# Main.net
KiCad netlist of a schematic drawn in Altium Designer
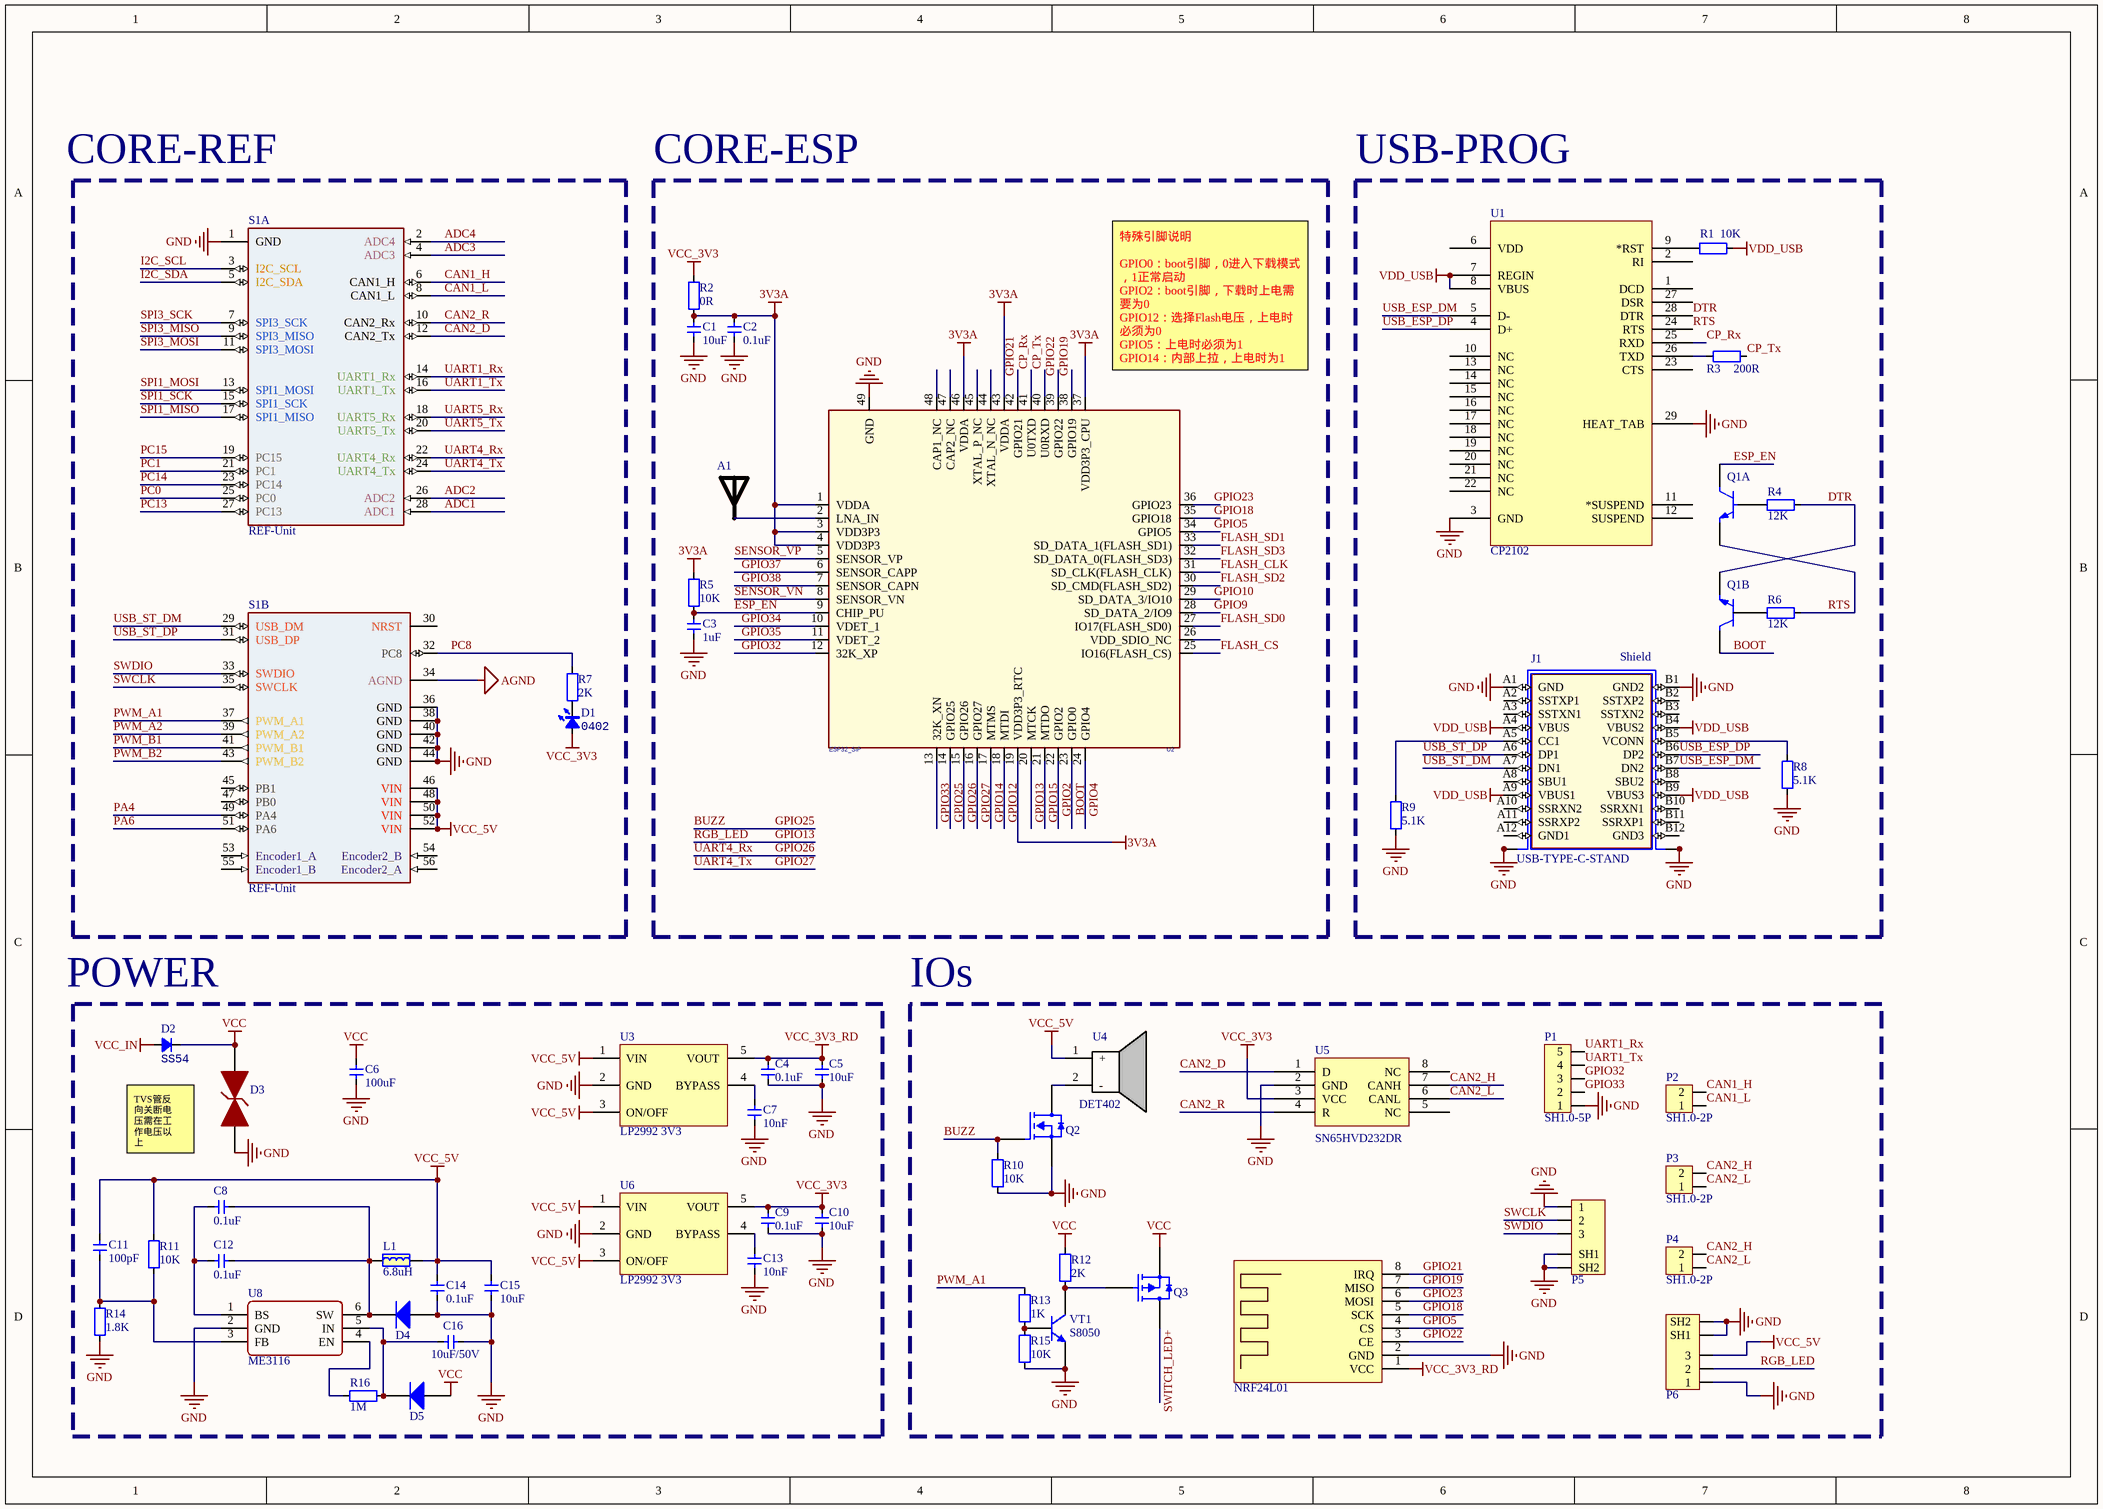
[diagram p0: Main.SchDoc]

(export (version "E")
  (design (tool "Eeschema 10.0.6"))
  (components
    (comp (ref "A1")
      (value "RAINSUN")
      (footprint "ANT-Rainsun-AN5120")
      (libsource (lib "MyPcbLib") (part "ANT-Rainsun-AP5120"))
    )
    (comp (ref "C1")
      (value "10uF")
      (footprint "CAP_0402")
      (description "Capacitor")
      (libsource (lib "MyPcbLib") (part "电容-0402"))
    )
    (comp (ref "C2")
      (value "0.1uF")
      (footprint "CAP_0402")
      (description "Capacitor")
      (libsource (lib "MyPcbLib") (part "电容-0402"))
    )
    (comp (ref "C3")
      (value "1uF")
      (footprint "CAP_0402")
      (description "Capacitor")
      (libsource (lib "MyPcbLib") (part "电容-0402"))
    )
    (comp (ref "C4")
      (value "0.1uF")
      (footprint "CAP_0402")
      (description "Capacitor")
      (libsource (lib "MyPcbLib") (part "电容-0402"))
    )
    (comp (ref "C5")
      (value "10uF")
      (footprint "CAP_0402")
      (description "Capacitor")
      (libsource (lib "MyPcbLib") (part "电容-0402"))
    )
    (comp (ref "C6")
      (value "100uF")
      (footprint "1206-CAP")
      (description "Capacitor")
      (libsource (lib "MyPcbLib") (part "电容-1206"))
    )
    (comp (ref "C7")
      (value "10nF")
      (footprint "CAP_0402")
      (description "Capacitor")
      (libsource (lib "MyPcbLib") (part "电容-0402"))
    )
    (comp (ref "C8")
      (value "0.1uF")
      (footprint "CAP_0402")
      (description "Capacitor")
      (libsource (lib "MyPcbLib") (part "电容-0402"))
    )
    (comp (ref "C9")
      (value "0.1uF")
      (footprint "CAP_0402")
      (description "Capacitor")
      (libsource (lib "MyPcbLib") (part "电容-0402"))
    )
    (comp (ref "C10")
      (value "10uF")
      (footprint "CAP_0402")
      (description "Capacitor")
      (libsource (lib "MyPcbLib") (part "电容-0402"))
    )
    (comp (ref "C11")
      (value "100pF")
      (footprint "CAP_0402")
      (description "Capacitor")
      (libsource (lib "MyPcbLib") (part "电容-0402"))
    )
    (comp (ref "C12")
      (value "0.1uF")
      (footprint "CAP_0402")
      (description "Capacitor")
      (libsource (lib "MyPcbLib") (part "电容-0402"))
    )
    (comp (ref "C13")
      (value "10nF")
      (footprint "CAP_0402")
      (description "Capacitor")
      (libsource (lib "MyPcbLib") (part "电容-0402"))
    )
    (comp (ref "C14")
      (value "0.1uF")
      (footprint "CAP_0402")
      (description "Capacitor")
      (libsource (lib "MyPcbLib") (part "电容-0402"))
    )
    (comp (ref "C15")
      (value "10uF")
      (footprint "CAP_0402")
      (description "Capacitor")
      (libsource (lib "MyPcbLib") (part "电容-0402"))
    )
    (comp (ref "C16")
      (value "10uF/50V")
      (footprint "CAP_0402")
      (description "Capacitor")
      (libsource (lib "MyPcbLib") (part "电容-0402"))
    )
    (comp (ref "D1")
      (value "color?")
      (footprint "LED_0402_RED")
      (description "LED")
      (fields (field (name "TYPE") "0402"))
      (libsource (lib "KitSprout") (part "LED_0402"))
    )
    (comp (ref "D2")
      (value "SS54")
      (footprint "DO-214AC")
      (description "Diode")
      (libsource (lib "KitSprout") (part "Diode_SMA"))
    )
    (comp (ref "D3")
      (value "SMBJ28CA")
      (footprint "SMBJ-CA_MFG")
      (libsource (lib "MyPcbLib") (part "SMBJ28CA"))
    )
    (comp (ref "D4")
      (value "二极管-5819W")
      (footprint "SOD-323")
      (description "40V")
      (libsource (lib "MyPcbLib") (part "二极管-5819W"))
    )
    (comp (ref "D5")
      (value "二极管-5819W")
      (footprint "SOD-323")
      (description "40V")
      (libsource (lib "MyPcbLib") (part "二极管-5819W"))
    )
    (comp (ref "J1")
      (value "USB-TYPE-C-STAND")
      (footprint "USB-TYPE-C-STAND")
      (fields (field (name "MP") "632722110112") (field (name "MF") "Wurth Electronics"))
      (libsource (lib "MyPcbLib") (part "USB-TYPE-C-STAND"))
    )
    (comp (ref "L1") (value "6.8uH") (footprint "IND-201612") (libsource (lib "MyPcbLib") (part "电感-201612")))
    (comp (ref "P1") (value "SH1.0-5P") (footprint "SH1.0-5P") (libsource (lib "MyPcbLib") (part "SH1.0-5P")))
    (comp (ref "P2") (value "SH1.0-2P") (footprint "SH1.0-2P") (libsource (lib "MyPcbLib") (part "SH1.0-2P")))
    (comp (ref "P3") (value "SH1.0-2P") (footprint "SH1.0-2P") (libsource (lib "MyPcbLib") (part "SH1.0-2P")))
    (comp (ref "P4") (value "SH1.0-2P") (footprint "SH1.0-2P") (libsource (lib "MyPcbLib") (part "SH1.0-2P")))
    (comp (ref "P5")
      (value "SH1.0-3P")
      (footprint "SH1.0-3P")
      (description "Header")
      (libsource (lib "") (part "SH1.0-3P_1"))
    )
    (comp (ref "P6")
      (value "SH1.0-3P")
      (footprint "SH1.0-3P")
      (description "Header")
      (libsource (lib "MyPcbLib") (part "SH1.0-3P"))
    )
    (comp (ref "Q1")
      (value "BC847BVC-7")
      (footprint "SOT563-6")
      (libsource (lib "MyPcbLib") (part "BC847BVC-7"))
    )
    (comp (ref "Q2")
      (value "AO3400A")
      (footprint "SOT23-3")
      (description "N-MOS")
      (libsource (lib "MyPcbLib") (part "AO3400A"))
    )
    (comp (ref "Q3")
      (value "AO3401A")
      (footprint "SOT23-3")
      (description "P-MOS")
      (libsource (lib "MyPcbLib") (part "AO3401A"))
    )
    (comp (ref "R1")
      (value "10K")
      (footprint "RES_0402")
      (description "Resistor")
      (libsource (lib "") (part "电阻-0402_1"))
    )
    (comp (ref "R2")
      (value "0R")
      (footprint "RES_0402")
      (description "Resistor")
      (libsource (lib "MyPcbLib") (part "电阻-0402"))
    )
    (comp (ref "R3")
      (value "200R")
      (footprint "RES_0402")
      (description "Resistor")
      (libsource (lib "") (part "电阻-0402_1"))
    )
    (comp (ref "R4")
      (value "12K")
      (footprint "RES_0402")
      (description "Resistor")
      (libsource (lib "") (part "电阻-0402_1"))
    )
    (comp (ref "R5")
      (value "10K")
      (footprint "RES_0402")
      (description "Resistor")
      (libsource (lib "MyPcbLib") (part "电阻-0402"))
    )
    (comp (ref "R6")
      (value "12K")
      (footprint "RES_0402")
      (description "Resistor")
      (libsource (lib "") (part "电阻-0402_1"))
    )
    (comp (ref "R7")
      (value "2K")
      (footprint "RES_0402")
      (description "Resistor")
      (libsource (lib "MyPcbLib") (part "电阻-0402"))
    )
    (comp (ref "R8")
      (value "5.1K")
      (footprint "RES_0402")
      (description "Resistor")
      (libsource (lib "MyPcbLib") (part "电阻-0402"))
    )
    (comp (ref "R9")
      (value "5.1K")
      (footprint "RES_0402")
      (description "Resistor")
      (libsource (lib "MyPcbLib") (part "电阻-0402"))
    )
    (comp (ref "R10")
      (value "10K")
      (footprint "RES_0402")
      (description "Resistor")
      (libsource (lib "") (part "电阻-0402_2"))
    )
    (comp (ref "R11")
      (value "10K")
      (footprint "RES_0402")
      (description "Resistor")
      (libsource (lib "") (part "电阻-0402_2"))
    )
    (comp (ref "R12")
      (value "2K")
      (footprint "RES_0402")
      (description "Resistor")
      (libsource (lib "") (part "电阻-0402_2"))
    )
    (comp (ref "R13")
      (value "1K")
      (footprint "RES_0402")
      (description "Resistor")
      (libsource (lib "MyPcbLib") (part "电阻-0402"))
    )
    (comp (ref "R14")
      (value "1.8K")
      (footprint "RES_0402")
      (description "Resistor")
      (libsource (lib "") (part "电阻-0402_2"))
    )
    (comp (ref "R15")
      (value "10K")
      (footprint "RES_0402")
      (description "Resistor")
      (libsource (lib "MyPcbLib") (part "电阻-0402"))
    )
    (comp (ref "R16")
      (value "1M")
      (footprint "RES_0402")
      (description "Resistor")
      (libsource (lib "") (part "电阻-0402_1"))
    )
    (comp (ref "S1")
      (value "REF-Unit")
      (footprint "REF-UNIT")
      (description "Robot Embedded Framework based on STM43F405RGT6.")
      (libsource (lib "SOM") (part "REF-Unit"))
    )
    (comp (ref "U1")
      (value "CP2102")
      (footprint "QFN-28")
      (description "USB转TTL")
      (libsource (lib "mLib") (part "CP2102"))
    )
    (comp (ref "U2")
      (value "ESP32_SIP")
      (footprint "QFN-48_7X7")
      (libsource (lib "mLib") (part "ESP32-PICO"))
    )
    (comp (ref "U3")
      (value "LP2992 3V3")
      (footprint "SOT23-5")
      (description "LDO")
      (libsource (lib "mLib") (part "LP2992"))
    )
    (comp (ref "U4") (value "DET402") (footprint "DET402") (libsource (lib "MyPcbLib") (part "DET402")))
    (comp (ref "U5")
      (value "SN65HVD232D")
      (footprint "SO-8")
      (fields
        (field (name "MANUFACTURER") "Texas Instruments")
        (field (name "MANUFACTURER PART NUMBER") "SN65HVD232DR")
      )
      (libsource (lib "MyPcbLib") (part "SN65HVD232D"))
    )
    (comp (ref "U6")
      (value "LP2992 3V3")
      (footprint "SOT23-5")
      (description "LDO")
      (libsource (lib "mLib") (part "LP2992"))
    )
    (comp (ref "U7")
      (value "NRF24L01")
      (footprint "NRF24L01-MODULE")
      (libsource (lib "MyPcbLib") (part "NRF24L01模块"))
    )
    (comp (ref "U8")
      (value "ME3116")
      (footprint "SOT23-6")
      (description "DC-DC")
      (libsource (lib "MyPcbLib") (part "ME3116"))
    )
    (comp (ref "VT1")
      (value "S8050")
      (footprint "SMT_TRIODE_NPN")
      (description "Surface mount NPN transistor, package SOT-23")
      (libsource (lib "MyPcbLib") (part "SMT_TRIODE_NPN"))
    )
  )
  (nets
    (net (code "1") (name "/ADC1") (class "Default")
      (node (ref "S1") (pin "28") (pinfunction "ADC1_28") (pintype "input"))
    )
    (net (code "2") (name "/ADC2") (class "Default")
      (node (ref "S1") (pin "26") (pinfunction "ADC2_26") (pintype "input"))
    )
    (net (code "3") (name "/ADC3") (class "Default")
      (node (ref "S1") (pin "4") (pinfunction "ADC3_4") (pintype "input"))
    )
    (net (code "4") (name "/ADC4") (class "Default")
      (node (ref "S1") (pin "2") (pinfunction "ADC4_2") (pintype "input"))
    )
    (net (code "5") (name "/BOOT") (class "Default")
      (node (ref "Q1") (pin "3") (pinfunction "C2_3") (pintype "passive"))
      (node (ref "U2") (pin "23") (pinfunction "GPIO0_23") (pintype "passive"))
    )
    (net (code "6") (name "/BUZZ") (class "Default")
      (node (ref "Q2") (pin "1") (pinfunction "G_1") (pintype "passive"))
      (node (ref "R10") (pin "2") (pinfunction "2_2") (pintype "passive"))
      (node (ref "U2") (pin "14") (pinfunction "GPIO25_14") (pintype "passive"))
    )
    (net (code "7") (name "/CAN1_H") (class "Default")
      (node (ref "P2") (pin "2") (pinfunction "2_2") (pintype "passive"))
      (node (ref "S1") (pin "6") (pinfunction "CAN1_H_6") (pintype "bidirectional"))
    )
    (net (code "8") (name "/CAN1_L") (class "Default")
      (node (ref "P2") (pin "1") (pinfunction "1_1") (pintype "passive"))
      (node (ref "S1") (pin "8") (pinfunction "CAN1_L_8") (pintype "bidirectional"))
    )
    (net (code "9") (name "/CAN2_D") (class "Default")
      (node (ref "S1") (pin "12") (pinfunction "CAN2_Tx_12") (pintype "bidirectional"))
      (node (ref "U5") (pin "1") (pinfunction "D_1") (pintype "passive"))
    )
    (net (code "10") (name "/CAN2_H") (class "Default")
      (node (ref "P3") (pin "2") (pinfunction "2_2") (pintype "passive"))
      (node (ref "P4") (pin "2") (pinfunction "2_2") (pintype "passive"))
      (node (ref "U5") (pin "7") (pinfunction "CANH_7") (pintype "passive"))
    )
    (net (code "11") (name "/CAN2_L") (class "Default")
      (node (ref "P3") (pin "1") (pinfunction "1_1") (pintype "passive"))
      (node (ref "P4") (pin "1") (pinfunction "1_1") (pintype "passive"))
      (node (ref "U5") (pin "6") (pinfunction "CANL_6") (pintype "passive"))
    )
    (net (code "12") (name "/CAN2_R") (class "Default")
      (node (ref "S1") (pin "10") (pinfunction "CAN2_Rx_10") (pintype "bidirectional"))
      (node (ref "U5") (pin "4") (pinfunction "R_4") (pintype "passive"))
    )
    (net (code "13") (name "/CP_Rx") (class "Default")
      (node (ref "U1") (pin "25") (pinfunction "RXD_25") (pintype "passive"))
      (node (ref "U2") (pin "41") (pinfunction "U0TXD_41") (pintype "power_in"))
    )
    (net (code "14") (name "/CP_Tx") (class "Default")
      (node (ref "R3") (pin "1") (pinfunction "1_1") (pintype "passive"))
      (node (ref "U2") (pin "40") (pinfunction "U0RXD_40") (pintype "power_in"))
    )
    (net (code "15") (name "/DTR") (class "Default")
      (node (ref "Q1") (pin "4") (pinfunction "E2_4") (pintype "passive"))
      (node (ref "R4") (pin "1") (pinfunction "1_1") (pintype "passive"))
      (node (ref "U1") (pin "28") (pinfunction "DTR_28") (pintype "passive"))
    )
    (net (code "16") (name "/ESP_EN") (class "Default")
      (node (ref "C3") (pin "1") (pinfunction "1_1") (pintype "passive"))
      (node (ref "Q1") (pin "6") (pinfunction "C1_6") (pintype "passive"))
      (node (ref "R5") (pin "2") (pinfunction "2_2") (pintype "passive"))
      (node (ref "U2") (pin "9") (pinfunction "CHIP_PU_9") (pintype "passive"))
    )
    (net (code "17") (name "/FLASH_CLK") (class "Default")
      (node (ref "U2") (pin "31") (pinfunction "SD_CLK(FLASH_CLK)_31") (pintype "passive"))
    )
    (net (code "18") (name "/FLASH_CS") (class "Default")
      (node (ref "U2") (pin "25") (pinfunction "IO16(FLASH_CS)_25") (pintype "passive"))
    )
    (net (code "19") (name "/FLASH_SD0") (class "Default")
      (node (ref "U2") (pin "27") (pinfunction "IO17(FLASH_SD0)_27") (pintype "passive"))
    )
    (net (code "20") (name "/FLASH_SD1") (class "Default")
      (node (ref "U2") (pin "33") (pinfunction "SD_DATA_1(FLASH_SD1)_33") (pintype "passive"))
    )
    (net (code "21") (name "/FLASH_SD2") (class "Default")
      (node (ref "U2") (pin "30") (pinfunction "SD_CMD(FLASH_SD2)_30") (pintype "passive"))
    )
    (net (code "22") (name "/FLASH_SD3") (class "Default")
      (node (ref "U2") (pin "32") (pinfunction "SD_DATA_0(FLASH_SD3)_32") (pintype "passive"))
    )
    (net (code "23") (name "/GPIO2") (class "Default")
      (node (ref "U2") (pin "22") (pinfunction "GPIO2_22") (pintype "passive"))
    )
    (net (code "24") (name "/GPIO4") (class "Default")
      (node (ref "U2") (pin "24") (pinfunction "GPIO4_24") (pintype "passive"))
    )
    (net (code "25") (name "/GPIO5") (class "Default")
      (node (ref "U2") (pin "34") (pinfunction "GPIO5_34") (pintype "passive"))
      (node (ref "U7") (pin "4") (pinfunction "CS_4") (pintype "passive"))
    )
    (net (code "26") (name "/GPIO9") (class "Default")
      (node (ref "U2") (pin "28") (pinfunction "SD_DATA_2/IO9_28") (pintype "passive"))
    )
    (net (code "27") (name "/GPIO10") (class "Default")
      (node (ref "U2") (pin "29") (pinfunction "SD_DATA_3/IO10_29") (pintype "passive"))
    )
    (net (code "28") (name "/GPIO12") (class "Default")
      (node (ref "U2") (pin "18") (pinfunction "MTDI_18") (pintype "passive"))
    )
    (net (code "29") (name "/GPIO13") (class "Default")
      (node (ref "P6") (pin "2") (pinfunction "2_2") (pintype "passive"))
      (node (ref "U2") (pin "20") (pinfunction "MTCK_20") (pintype "passive"))
    )
    (net (code "30") (name "/GPIO14") (class "Default")
      (node (ref "U2") (pin "17") (pinfunction "MTMS_17") (pintype "passive"))
    )
    (net (code "31") (name "/GPIO15") (class "Default")
      (node (ref "U2") (pin "21") (pinfunction "MTDO_21") (pintype "passive"))
    )
    (net (code "32") (name "/GPIO18") (class "Default")
      (node (ref "U2") (pin "35") (pinfunction "GPIO18_35") (pintype "passive"))
      (node (ref "U7") (pin "5") (pinfunction "SCK_5") (pintype "passive"))
    )
    (net (code "33") (name "/GPIO19") (class "Default")
      (node (ref "U2") (pin "38") (pinfunction "GPIO19_38") (pintype "passive"))
      (node (ref "U7") (pin "7") (pinfunction "MISO_7") (pintype "passive"))
    )
    (net (code "34") (name "/GPIO21") (class "Default")
      (node (ref "U2") (pin "42") (pinfunction "GPIO21_42") (pintype "passive"))
      (node (ref "U7") (pin "8") (pinfunction "IRQ_8") (pintype "passive"))
    )
    (net (code "35") (name "/GPIO22") (class "Default")
      (node (ref "U2") (pin "39") (pinfunction "GPIO22_39") (pintype "passive"))
      (node (ref "U7") (pin "3") (pinfunction "CE_3") (pintype "passive"))
    )
    (net (code "36") (name "/GPIO23") (class "Default")
      (node (ref "U2") (pin "36") (pinfunction "GPIO23_36") (pintype "passive"))
      (node (ref "U7") (pin "6") (pinfunction "MOSI_6") (pintype "passive"))
    )
    (net (code "37") (name "/GPIO26") (class "Default")
      (node (ref "S1") (pin "22") (pinfunction "UART4_Rx_22") (pintype "bidirectional"))
      (node (ref "U2") (pin "15") (pinfunction "GPIO26_15") (pintype "passive"))
    )
    (net (code "38") (name "/GPIO27") (class "Default")
      (node (ref "S1") (pin "24") (pinfunction "UART4_Tx_24") (pintype "bidirectional"))
      (node (ref "U2") (pin "16") (pinfunction "GPIO27_16") (pintype "passive"))
    )
    (net (code "39") (name "/GPIO32") (class "Default")
      (node (ref "P1") (pin "3") (pinfunction "3_3") (pintype "passive"))
      (node (ref "U2") (pin "12") (pinfunction "32K_XP_12") (pintype "passive"))
    )
    (net (code "40") (name "/GPIO33") (class "Default")
      (node (ref "P1") (pin "2") (pinfunction "2_2") (pintype "passive"))
      (node (ref "U2") (pin "13") (pinfunction "32K_XN_13") (pintype "passive"))
    )
    (net (code "41") (name "/GPIO34") (class "Default")
      (node (ref "U2") (pin "10") (pinfunction "VDET_1_10") (pintype "passive"))
    )
    (net (code "42") (name "/GPIO35") (class "Default")
      (node (ref "U2") (pin "11") (pinfunction "VDET_2_11") (pintype "passive"))
    )
    (net (code "43") (name "/GPIO37") (class "Default")
      (node (ref "U2") (pin "6") (pinfunction "SENSOR_CAPP_6") (pintype "passive"))
    )
    (net (code "44") (name "/GPIO38") (class "Default")
      (node (ref "U2") (pin "7") (pinfunction "SENSOR_CAPN_7") (pintype "passive"))
    )
    (net (code "45") (name "/I2C_SCL") (class "Default")
      (node (ref "S1") (pin "3") (pinfunction "I2C_SCL_3") (pintype "bidirectional"))
    )
    (net (code "46") (name "/I2C_SDA") (class "Default")
      (node (ref "S1") (pin "5") (pinfunction "I2C_SDA_5") (pintype "bidirectional"))
    )
    (net (code "47") (name "/PA4") (class "Default")
      (node (ref "S1") (pin "49") (pinfunction "PA4_49") (pintype "bidirectional"))
    )
    (net (code "48") (name "/PA6") (class "Default")
      (node (ref "S1") (pin "51") (pinfunction "PA6_51") (pintype "bidirectional"))
    )
    (net (code "49") (name "/PC0") (class "Default")
      (node (ref "S1") (pin "25") (pinfunction "PC0_25") (pintype "bidirectional"))
    )
    (net (code "50") (name "/PC1") (class "Default")
      (node (ref "S1") (pin "21") (pinfunction "PC1_21") (pintype "bidirectional"))
    )
    (net (code "51") (name "/PC8") (class "Default")
      (node (ref "R7") (pin "1") (pinfunction "1_1") (pintype "passive"))
      (node (ref "S1") (pin "32") (pinfunction "PC8_32") (pintype "bidirectional"))
    )
    (net (code "52") (name "/PC13") (class "Default")
      (node (ref "S1") (pin "27") (pinfunction "PC13_27") (pintype "bidirectional"))
    )
    (net (code "53") (name "/PC14") (class "Default")
      (node (ref "S1") (pin "23") (pinfunction "PC14_23") (pintype "bidirectional"))
    )
    (net (code "54") (name "/PC15") (class "Default")
      (node (ref "S1") (pin "19") (pinfunction "PC15_19") (pintype "bidirectional"))
    )
    (net (code "55") (name "/PWM_A1") (class "Default")
      (node (ref "R13") (pin "1") (pinfunction "1_1") (pintype "passive"))
      (node (ref "S1") (pin "37") (pinfunction "PWM_A1_37") (pintype "output"))
    )
    (net (code "56") (name "/PWM_A2") (class "Default")
      (node (ref "S1") (pin "39") (pinfunction "PWM_A2_39") (pintype "output"))
    )
    (net (code "57") (name "/PWM_B1") (class "Default")
      (node (ref "S1") (pin "41") (pinfunction "PWM_B1_41") (pintype "output"))
    )
    (net (code "58") (name "/PWM_B2") (class "Default")
      (node (ref "S1") (pin "43") (pinfunction "PWM_B2_43") (pintype "output"))
    )
    (net (code "59") (name "/RTS") (class "Default")
      (node (ref "Q1") (pin "1") (pinfunction "E1_1") (pintype "passive"))
      (node (ref "R6") (pin "1") (pinfunction "1_1") (pintype "passive"))
      (node (ref "U1") (pin "24") (pinfunction "RTS_24") (pintype "passive"))
    )
    (net (code "60") (name "/SENSOR_VN") (class "Default")
      (node (ref "U2") (pin "8") (pinfunction "SENSOR_VN_8") (pintype "passive"))
    )
    (net (code "61") (name "/SENSOR_VP") (class "Default")
      (node (ref "U2") (pin "5") (pinfunction "SENSOR_VP_5") (pintype "passive"))
    )
    (net (code "62") (name "/SPI1_MISO") (class "Default")
      (node (ref "S1") (pin "17") (pinfunction "SPI1_MISO_17") (pintype "bidirectional"))
    )
    (net (code "63") (name "/SPI1_MOSI") (class "Default")
      (node (ref "S1") (pin "13") (pinfunction "SPI1_MOSI_13") (pintype "bidirectional"))
    )
    (net (code "64") (name "/SPI1_SCK") (class "Default")
      (node (ref "S1") (pin "15") (pinfunction "SPI1_SCK_15") (pintype "bidirectional"))
    )
    (net (code "65") (name "/SPI3_MISO") (class "Default")
      (node (ref "S1") (pin "9") (pinfunction "SPI3_MISO_9") (pintype "bidirectional"))
    )
    (net (code "66") (name "/SPI3_MOSI") (class "Default")
      (node (ref "S1") (pin "11") (pinfunction "SPI3_MOSI_11") (pintype "bidirectional"))
    )
    (net (code "67") (name "/SPI3_SCK") (class "Default")
      (node (ref "S1") (pin "7") (pinfunction "SPI3_SCK_7") (pintype "bidirectional"))
    )
    (net (code "68") (name "/SWCLK") (class "Default")
      (node (ref "P5") (pin "2") (pinfunction "2_2") (pintype "passive"))
      (node (ref "S1") (pin "35") (pinfunction "SWCLK_35") (pintype "bidirectional"))
    )
    (net (code "69") (name "/SWDIO") (class "Default")
      (node (ref "P5") (pin "3") (pinfunction "3_3") (pintype "passive"))
      (node (ref "S1") (pin "33") (pinfunction "SWDIO_33") (pintype "bidirectional"))
    )
    (net (code "70") (name "/SWITCH_LED+") (class "Default")
      (node (ref "Q3") (pin "3") (pinfunction "D_3") (pintype "passive"))
    )
    (net (code "71") (name "/UART1_Rx") (class "Default")
      (node (ref "P1") (pin "5") (pinfunction "5_5") (pintype "passive"))
      (node (ref "S1") (pin "14") (pinfunction "UART1_Rx_14") (pintype "bidirectional"))
    )
    (net (code "72") (name "/UART1_Tx") (class "Default")
      (node (ref "P1") (pin "4") (pinfunction "4_4") (pintype "passive"))
      (node (ref "S1") (pin "16") (pinfunction "UART1_Tx_16") (pintype "bidirectional"))
    )
    (net (code "73") (name "/UART5_Rx") (class "Default")
      (node (ref "S1") (pin "18") (pinfunction "UART5_Rx_18") (pintype "bidirectional"))
    )
    (net (code "74") (name "/UART5_Tx") (class "Default")
      (node (ref "S1") (pin "20") (pinfunction "UART5_Tx_20") (pintype "bidirectional"))
    )
    (net (code "75") (name "/USB_ESP_DM") (class "Default")
      (node (ref "J1") (pin "B7") (pinfunction "DN2_B7") (pintype "bidirectional"))
      (node (ref "U1") (pin "5") (pinfunction "D-_5") (pintype "passive"))
    )
    (net (code "76") (name "/USB_ESP_DP") (class "Default")
      (node (ref "J1") (pin "B6") (pinfunction "DP2_B6") (pintype "bidirectional"))
      (node (ref "U1") (pin "4") (pinfunction "D+_4") (pintype "passive"))
    )
    (net (code "77") (name "/USB_ST_DM") (class "Default")
      (node (ref "J1") (pin "A7") (pinfunction "DN1_A7") (pintype "bidirectional"))
      (node (ref "S1") (pin "29") (pinfunction "USB_DM_29") (pintype "bidirectional"))
    )
    (net (code "78") (name "/USB_ST_DP") (class "Default")
      (node (ref "J1") (pin "A6") (pinfunction "DP1_A6") (pintype "bidirectional"))
      (node (ref "S1") (pin "31") (pinfunction "USB_DP_31") (pintype "bidirectional"))
    )
    (net (code "79") (name "3V3A") (class "Default")
      (node (ref "C1") (pin "2") (pinfunction "2_2") (pintype "passive"))
      (node (ref "C2") (pin "2") (pinfunction "2_2") (pintype "passive"))
      (node (ref "R2") (pin "2") (pinfunction "2_2") (pintype "passive"))
      (node (ref "R5") (pin "1") (pinfunction "1_1") (pintype "passive"))
      (node (ref "U2") (pin "1") (pinfunction "VDDA_1") (pintype "power_in"))
      (node (ref "U2") (pin "19") (pinfunction "VDD3P3_RTC_19") (pintype "power_in"))
      (node (ref "U2") (pin "3") (pinfunction "VDD3P3_3") (pintype "power_in"))
      (node (ref "U2") (pin "37") (pinfunction "VDD3P3_CPU_37") (pintype "power_in"))
      (node (ref "U2") (pin "4") (pinfunction "VDD3P3_4") (pintype "power_in"))
      (node (ref "U2") (pin "43") (pinfunction "VDDA_43") (pintype "power_in"))
      (node (ref "U2") (pin "46") (pinfunction "VDDA_46") (pintype "power_in"))
    )
    (net (code "80") (name "AGND") (class "Default")
      (node (ref "S1") (pin "34") (pinfunction "AGND_34") (pintype "power_in"))
    )
    (net (code "81") (name "GND") (class "Default")
      (node (ref "C1") (pin "1") (pinfunction "1_1") (pintype "passive"))
      (node (ref "C10") (pin "1") (pinfunction "1_1") (pintype "passive"))
      (node (ref "C13") (pin "1") (pinfunction "1_1") (pintype "passive"))
      (node (ref "C14") (pin "1") (pinfunction "1_1") (pintype "passive"))
      (node (ref "C15") (pin "1") (pinfunction "1_1") (pintype "passive"))
      (node (ref "C16") (pin "1") (pinfunction "1_1") (pintype "passive"))
      (node (ref "C2") (pin "1") (pinfunction "1_1") (pintype "passive"))
      (node (ref "C3") (pin "2") (pinfunction "2_2") (pintype "passive"))
      (node (ref "C4") (pin "1") (pinfunction "1_1") (pintype "passive"))
      (node (ref "C5") (pin "1") (pinfunction "1_1") (pintype "passive"))
      (node (ref "C6") (pin "1") (pinfunction "1_1") (pintype "passive"))
      (node (ref "C7") (pin "1") (pinfunction "1_1") (pintype "passive"))
      (node (ref "C9") (pin "1") (pinfunction "1_1") (pintype "passive"))
      (node (ref "D3") (pin "1") (pinfunction "1_1") (pintype "passive"))
      (node (ref "D4") (pin "1") (pinfunction "A_1") (pintype "passive"))
      (node (ref "J1") (pin "A1") (pinfunction "GND_A1") (pintype "bidirectional"))
      (node (ref "J1") (pin "B1") (pinfunction "GND2_B1") (pintype "bidirectional"))
      (node (ref "J1") (pin "S1") (pinfunction "SHIELD_S1") (pintype "bidirectional"))
      (node (ref "J1") (pin "S2") (pinfunction "SHIELD_S2") (pintype "bidirectional"))
      (node (ref "J1") (pin "S3") (pinfunction "SHIELD1_S3") (pintype "bidirectional"))
      (node (ref "J1") (pin "S4") (pinfunction "SHIELD1_S4") (pintype "bidirectional"))
      (node (ref "P1") (pin "1") (pinfunction "1_1") (pintype "passive"))
      (node (ref "P5") (pin "1") (pinfunction "1_1") (pintype "passive"))
      (node (ref "P5") (pin "SH1") (pinfunction "SH1_SH1") (pintype "passive"))
      (node (ref "P5") (pin "SH2") (pinfunction "SH2_SH2") (pintype "passive"))
      (node (ref "P6") (pin "1") (pinfunction "1_1") (pintype "passive"))
      (node (ref "P6") (pin "SH1") (pinfunction "SH1_SH1") (pintype "passive"))
      (node (ref "P6") (pin "SH2") (pinfunction "SH2_SH2") (pintype "passive"))
      (node (ref "Q2") (pin "2") (pinfunction "S_2") (pintype "passive"))
      (node (ref "R10") (pin "1") (pinfunction "1_1") (pintype "passive"))
      (node (ref "R14") (pin "1") (pinfunction "1_1") (pintype "passive"))
      (node (ref "R15") (pin "2") (pinfunction "2_2") (pintype "passive"))
      (node (ref "R8") (pin "2") (pinfunction "2_2") (pintype "passive"))
      (node (ref "R9") (pin "2") (pinfunction "2_2") (pintype "passive"))
      (node (ref "S1") (pin "1") (pinfunction "GND_1") (pintype "power_in"))
      (node (ref "S1") (pin "36") (pinfunction "GND_36") (pintype "power_in"))
      (node (ref "S1") (pin "38") (pinfunction "GND_38") (pintype "power_in"))
      (node (ref "S1") (pin "40") (pinfunction "GND_40") (pintype "power_in"))
      (node (ref "S1") (pin "42") (pinfunction "GND_42") (pintype "power_in"))
      (node (ref "S1") (pin "44") (pinfunction "GND_44") (pintype "power_in"))
      (node (ref "U1") (pin "29") (pinfunction "HEAT_TAB_29") (pintype "passive"))
      (node (ref "U1") (pin "3") (pinfunction "GND_3") (pintype "passive"))
      (node (ref "U2") (pin "49") (pinfunction "GND_49") (pintype "power_in"))
      (node (ref "U3") (pin "2") (pinfunction "GND_2") (pintype "passive"))
      (node (ref "U5") (pin "2") (pinfunction "GND_2") (pintype "passive"))
      (node (ref "U6") (pin "2") (pinfunction "GND_2") (pintype "passive"))
      (node (ref "U7") (pin "2") (pinfunction "GND_2") (pintype "passive"))
      (node (ref "U8") (pin "2") (pinfunction "GND_2") (pintype "passive"))
      (node (ref "VT1") (pin "2") (pinfunction "E_2") (pintype "passive"))
    )
    (net (code "82") (name "Net-(D1-K)") (class "Default")
      (node (ref "D1") (pin "2") (pinfunction "K_2") (pintype "passive"))
      (node (ref "R7") (pin "2") (pinfunction "2_2") (pintype "passive"))
    )
    (net (code "83") (name "Net-(D4-K)") (class "Default")
      (node (ref "C12") (pin "1") (pinfunction "1_1") (pintype "passive"))
      (node (ref "C8") (pin "1") (pinfunction "1_1") (pintype "passive"))
      (node (ref "D4") (pin "2") (pinfunction "K_2") (pintype "passive"))
      (node (ref "L1") (pin "1") (pintype "passive"))
      (node (ref "U8") (pin "6") (pinfunction "SW_6") (pintype "passive"))
    )
    (net (code "84") (name "Net-(D5-K)") (class "Default")
      (node (ref "C16") (pin "2") (pinfunction "2_2") (pintype "passive"))
      (node (ref "D5") (pin "2") (pinfunction "K_2") (pintype "passive"))
      (node (ref "R16") (pin "1") (pinfunction "1_1") (pintype "passive"))
      (node (ref "U8") (pin "5") (pinfunction "IN_5") (pintype "passive"))
    )
    (net (code "85") (name "Net-(J1-CC1)") (class "Default")
      (node (ref "J1") (pin "A5") (pinfunction "CC1_A5") (pintype "bidirectional"))
      (node (ref "R9") (pin "1") (pinfunction "1_1") (pintype "passive"))
    )
    (net (code "86") (name "Net-(J1-VCONN)") (class "Default")
      (node (ref "J1") (pin "B5") (pinfunction "VCONN_B5") (pintype "bidirectional"))
      (node (ref "R8") (pin "1") (pinfunction "1_1") (pintype "passive"))
    )
    (net (code "87") (name "Net-(Q1A-B1)") (class "Default")
      (node (ref "Q1") (pin "2") (pinfunction "B1_2") (pintype "passive"))
      (node (ref "R4") (pin "2") (pinfunction "2_2") (pintype "passive"))
    )
    (net (code "88") (name "Net-(Q1B-B2)") (class "Default")
      (node (ref "Q1") (pin "5") (pinfunction "B2_5") (pintype "passive"))
      (node (ref "R6") (pin "2") (pinfunction "2_2") (pintype "passive"))
    )
    (net (code "89") (name "Net-(Q2-D)") (class "Default")
      (node (ref "Q2") (pin "3") (pinfunction "D_3") (pintype "passive"))
      (node (ref "U4") (pin "2") (pinfunction "-_2") (pintype "passive"))
    )
    (net (code "90") (name "Net-(Q3-G)") (class "Default")
      (node (ref "Q3") (pin "1") (pinfunction "G_1") (pintype "passive"))
      (node (ref "R12") (pin "1") (pinfunction "1_1") (pintype "passive"))
      (node (ref "VT1") (pin "3") (pinfunction "C_3") (pintype "passive"))
    )
    (net (code "91") (name "Net-(U1-*RST)") (class "Default")
      (node (ref "R1") (pin "2") (pinfunction "2_2") (pintype "passive"))
      (node (ref "U1") (pin "9") (pinfunction "*RST_9") (pintype "passive"))
    )
    (net (code "92") (name "Net-(U1-TXD)") (class "Default")
      (node (ref "R3") (pin "2") (pinfunction "2_2") (pintype "passive"))
      (node (ref "U1") (pin "26") (pinfunction "TXD_26") (pintype "passive"))
    )
    (net (code "93") (name "Net-(U2-LNA_IN)") (class "Default")
      (node (ref "A1") (pin "1") (pinfunction "1_1") (pintype "passive"))
      (node (ref "U2") (pin "2") (pinfunction "LNA_IN_2") (pintype "passive"))
    )
    (net (code "94") (name "Net-(U3-BYPASS)") (class "Default")
      (node (ref "C7") (pin "2") (pinfunction "2_2") (pintype "passive"))
      (node (ref "U3") (pin "4") (pinfunction "BYPASS_4") (pintype "passive"))
    )
    (net (code "95") (name "Net-(U6-BYPASS)") (class "Default")
      (node (ref "C13") (pin "2") (pinfunction "2_2") (pintype "passive"))
      (node (ref "U6") (pin "4") (pinfunction "BYPASS_4") (pintype "passive"))
    )
    (net (code "96") (name "Net-(U8-BS)") (class "Default")
      (node (ref "C12") (pin "2") (pinfunction "2_2") (pintype "passive"))
      (node (ref "C8") (pin "2") (pinfunction "2_2") (pintype "passive"))
      (node (ref "U8") (pin "1") (pinfunction "BS_1") (pintype "passive"))
    )
    (net (code "97") (name "Net-(U8-EN)") (class "Default")
      (node (ref "R16") (pin "2") (pinfunction "2_2") (pintype "passive"))
      (node (ref "U8") (pin "4") (pinfunction "EN_4") (pintype "passive"))
    )
    (net (code "98") (name "Net-(U8-FB)") (class "Default")
      (node (ref "C11") (pin "2") (pinfunction "2_2") (pintype "passive"))
      (node (ref "R11") (pin "1") (pinfunction "1_1") (pintype "passive"))
      (node (ref "R14") (pin "2") (pinfunction "2_2") (pintype "passive"))
      (node (ref "U8") (pin "3") (pinfunction "FB_3") (pintype "passive"))
    )
    (net (code "99") (name "Net-(VT1-B)") (class "Default")
      (node (ref "R13") (pin "2") (pinfunction "2_2") (pintype "passive"))
      (node (ref "R15") (pin "1") (pinfunction "1_1") (pintype "passive"))
      (node (ref "VT1") (pin "1") (pinfunction "B_1") (pintype "passive"))
    )
    (net (code "100") (name "VCC") (class "Default")
      (node (ref "C6") (pin "2") (pinfunction "2_2") (pintype "passive"))
      (node (ref "D2") (pin "2") (pinfunction "K_2") (pintype "passive"))
      (node (ref "D3") (pin "2") (pinfunction "2_2") (pintype "passive"))
      (node (ref "D5") (pin "1") (pinfunction "A_1") (pintype "passive"))
      (node (ref "Q3") (pin "2") (pinfunction "S_2") (pintype "passive"))
      (node (ref "R12") (pin "2") (pinfunction "2_2") (pintype "passive"))
    )
    (net (code "101") (name "VCC_3V3") (class "Default")
      (node (ref "C10") (pin "2") (pinfunction "2_2") (pintype "passive"))
      (node (ref "C9") (pin "2") (pinfunction "2_2") (pintype "passive"))
      (node (ref "D1") (pin "1") (pinfunction "A_1") (pintype "passive"))
      (node (ref "R2") (pin "1") (pinfunction "1_1") (pintype "passive"))
      (node (ref "U5") (pin "3") (pinfunction "VCC_3") (pintype "passive"))
      (node (ref "U6") (pin "5") (pinfunction "VOUT_5") (pintype "passive"))
    )
    (net (code "102") (name "VCC_3V3_RD") (class "Default")
      (node (ref "C4") (pin "2") (pinfunction "2_2") (pintype "passive"))
      (node (ref "C5") (pin "2") (pinfunction "2_2") (pintype "passive"))
      (node (ref "U3") (pin "5") (pinfunction "VOUT_5") (pintype "passive"))
      (node (ref "U7") (pin "1") (pinfunction "VCC_1") (pintype "passive"))
    )
    (net (code "103") (name "VCC_5V") (class "Default")
      (node (ref "C11") (pin "1") (pinfunction "1_1") (pintype "passive"))
      (node (ref "C14") (pin "2") (pinfunction "2_2") (pintype "passive"))
      (node (ref "C15") (pin "2") (pinfunction "2_2") (pintype "passive"))
      (node (ref "L1") (pin "2") (pinfunction "2_2") (pintype "passive"))
      (node (ref "P6") (pin "3") (pinfunction "3_3") (pintype "passive"))
      (node (ref "R11") (pin "2") (pinfunction "2_2") (pintype "passive"))
      (node (ref "S1") (pin "46") (pinfunction "VIN_46") (pintype "power_in"))
      (node (ref "S1") (pin "48") (pinfunction "VIN_48") (pintype "power_in"))
      (node (ref "S1") (pin "50") (pinfunction "VIN_50") (pintype "power_in"))
      (node (ref "S1") (pin "52") (pinfunction "VIN_52") (pintype "power_in"))
      (node (ref "U3") (pin "1") (pinfunction "VIN_1") (pintype "passive"))
      (node (ref "U3") (pin "3") (pinfunction "ON/OFF_3") (pintype "passive"))
      (node (ref "U4") (pin "1") (pinfunction "+_1") (pintype "passive"))
      (node (ref "U6") (pin "1") (pinfunction "VIN_1") (pintype "passive"))
      (node (ref "U6") (pin "3") (pinfunction "ON/OFF_3") (pintype "passive"))
    )
    (net (code "104") (name "VCC_IN") (class "Default")
      (node (ref "D2") (pin "1") (pinfunction "A_1") (pintype "passive"))
    )
    (net (code "105") (name "VDD_USB") (class "Default")
      (node (ref "J1") (pin "A4") (pinfunction "VBUS_A4") (pintype "bidirectional"))
      (node (ref "J1") (pin "A9") (pinfunction "VBUS1_A9") (pintype "bidirectional"))
      (node (ref "J1") (pin "B4") (pinfunction "VBUS2_B4") (pintype "bidirectional"))
      (node (ref "J1") (pin "B9") (pinfunction "VBUS3_B9") (pintype "bidirectional"))
      (node (ref "R1") (pin "1") (pinfunction "1_1") (pintype "passive"))
      (node (ref "U1") (pin "7") (pinfunction "REGIN_7") (pintype "passive"))
      (node (ref "U1") (pin "8") (pinfunction "VBUS_8") (pintype "passive"))
    )
    (net (code "106") (name "unconnected-(J1-GND1-PadA12)") (class "Default")
      (node (ref "J1") (pin "A12") (pinfunction "GND1_A12") (pintype "bidirectional"))
    )
    (net (code "107") (name "unconnected-(J1-GND3-PadB12)") (class "Default")
      (node (ref "J1") (pin "B12") (pinfunction "GND3_B12") (pintype "bidirectional"))
    )
    (net (code "108") (name "unconnected-(J1-SBU1-PadA8)") (class "Default")
      (node (ref "J1") (pin "A8") (pinfunction "SBU1_A8") (pintype "bidirectional"))
    )
    (net (code "109") (name "unconnected-(J1-SBU2-PadB8)") (class "Default")
      (node (ref "J1") (pin "B8") (pinfunction "SBU2_B8") (pintype "bidirectional"))
    )
    (net (code "110") (name "unconnected-(J1-SSRXN1-PadB10)") (class "Default")
      (node (ref "J1") (pin "B10") (pinfunction "SSRXN1_B10") (pintype "bidirectional"))
    )
    (net (code "111") (name "unconnected-(J1-SSRXN2-PadA10)") (class "Default")
      (node (ref "J1") (pin "A10") (pinfunction "SSRXN2_A10") (pintype "bidirectional"))
    )
    (net (code "112") (name "unconnected-(J1-SSRXP1-PadB11)") (class "Default")
      (node (ref "J1") (pin "B11") (pinfunction "SSRXP1_B11") (pintype "bidirectional"))
    )
    (net (code "113") (name "unconnected-(J1-SSRXP2-PadA11)") (class "Default")
      (node (ref "J1") (pin "A11") (pinfunction "SSRXP2_A11") (pintype "bidirectional"))
    )
    (net (code "114") (name "unconnected-(J1-SSTXN1-PadA3)") (class "Default")
      (node (ref "J1") (pin "A3") (pinfunction "SSTXN1_A3") (pintype "bidirectional"))
    )
    (net (code "115") (name "unconnected-(J1-SSTXN2-PadB3)") (class "Default")
      (node (ref "J1") (pin "B3") (pinfunction "SSTXN2_B3") (pintype "bidirectional"))
    )
    (net (code "116") (name "unconnected-(J1-SSTXP1-PadA2)") (class "Default")
      (node (ref "J1") (pin "A2") (pinfunction "SSTXP1_A2") (pintype "bidirectional"))
    )
    (net (code "117") (name "unconnected-(J1-SSTXP2-PadB2)") (class "Default")
      (node (ref "J1") (pin "B2") (pinfunction "SSTXP2_B2") (pintype "bidirectional"))
    )
    (net (code "118") (name "unconnected-(S1B-Encoder1_A-Pad53)") (class "Default")
      (node (ref "S1") (pin "53") (pinfunction "Encoder1_A_53") (pintype "input"))
    )
    (net (code "119") (name "unconnected-(S1B-Encoder1_B-Pad55)") (class "Default")
      (node (ref "S1") (pin "55") (pinfunction "Encoder1_B_55") (pintype "input"))
    )
    (net (code "120") (name "unconnected-(S1B-Encoder2_A-Pad56)") (class "Default")
      (node (ref "S1") (pin "56") (pinfunction "Encoder2_A_56") (pintype "input"))
    )
    (net (code "121") (name "unconnected-(S1B-Encoder2_B-Pad54)") (class "Default")
      (node (ref "S1") (pin "54") (pinfunction "Encoder2_B_54") (pintype "input"))
    )
    (net (code "122") (name "unconnected-(S1B-NRST-Pad30)") (class "Default")
      (node (ref "S1") (pin "30") (pinfunction "NRST_30") (pintype "power_in"))
    )
    (net (code "123") (name "unconnected-(S1B-PB0-Pad47)") (class "Default")
      (node (ref "S1") (pin "47") (pinfunction "PB0_47") (pintype "bidirectional"))
    )
    (net (code "124") (name "unconnected-(S1B-PB1-Pad45)") (class "Default")
      (node (ref "S1") (pin "45") (pinfunction "PB1_45") (pintype "bidirectional"))
    )
    (net (code "125") (name "unconnected-(U1-*SUSPEND-Pad11)") (class "Default")
      (node (ref "U1") (pin "11") (pinfunction "*SUSPEND_11") (pintype "passive"))
    )
    (net (code "126") (name "unconnected-(U1-CTS-Pad23)") (class "Default")
      (node (ref "U1") (pin "23") (pinfunction "CTS_23") (pintype "passive"))
    )
    (net (code "127") (name "unconnected-(U1-DCD-Pad1)") (class "Default")
      (node (ref "U1") (pin "1") (pinfunction "DCD_1") (pintype "passive"))
    )
    (net (code "128") (name "unconnected-(U1-DSR-Pad27)") (class "Default")
      (node (ref "U1") (pin "27") (pinfunction "DSR_27") (pintype "passive"))
    )
    (net (code "129") (name "unconnected-(U1-NC-Pad10)") (class "Default")
      (node (ref "U1") (pin "10") (pinfunction "NC_10") (pintype "passive"))
    )
    (net (code "130") (name "unconnected-(U1-NC-Pad13)") (class "Default")
      (node (ref "U1") (pin "13") (pinfunction "NC_13") (pintype "passive"))
    )
    (net (code "131") (name "unconnected-(U1-NC-Pad14)") (class "Default")
      (node (ref "U1") (pin "14") (pinfunction "NC_14") (pintype "passive"))
    )
    (net (code "132") (name "unconnected-(U1-NC-Pad15)") (class "Default")
      (node (ref "U1") (pin "15") (pinfunction "NC_15") (pintype "passive"))
    )
    (net (code "133") (name "unconnected-(U1-NC-Pad16)") (class "Default")
      (node (ref "U1") (pin "16") (pinfunction "NC_16") (pintype "passive"))
    )
    (net (code "134") (name "unconnected-(U1-NC-Pad17)") (class "Default")
      (node (ref "U1") (pin "17") (pinfunction "NC_17") (pintype "passive"))
    )
    (net (code "135") (name "unconnected-(U1-NC-Pad18)") (class "Default")
      (node (ref "U1") (pin "18") (pinfunction "NC_18") (pintype "passive"))
    )
    (net (code "136") (name "unconnected-(U1-NC-Pad19)") (class "Default")
      (node (ref "U1") (pin "19") (pinfunction "NC_19") (pintype "passive"))
    )
    (net (code "137") (name "unconnected-(U1-NC-Pad20)") (class "Default")
      (node (ref "U1") (pin "20") (pinfunction "NC_20") (pintype "passive"))
    )
    (net (code "138") (name "unconnected-(U1-NC-Pad21)") (class "Default")
      (node (ref "U1") (pin "21") (pinfunction "NC_21") (pintype "passive"))
    )
    (net (code "139") (name "unconnected-(U1-NC-Pad22)") (class "Default")
      (node (ref "U1") (pin "22") (pinfunction "NC_22") (pintype "passive"))
    )
    (net (code "140") (name "unconnected-(U1-RI-Pad2)") (class "Default")
      (node (ref "U1") (pin "2") (pinfunction "RI_2") (pintype "passive"))
    )
    (net (code "141") (name "unconnected-(U1-SUSPEND-Pad12)") (class "Default")
      (node (ref "U1") (pin "12") (pinfunction "SUSPEND_12") (pintype "passive"))
    )
    (net (code "142") (name "unconnected-(U1-VDD-Pad6)") (class "Default")
      (node (ref "U1") (pin "6") (pinfunction "VDD_6") (pintype "passive"))
    )
    (net (code "143") (name "unconnected-(U2-CAP1_NC-Pad48)") (class "Default")
      (node (ref "U2") (pin "48") (pinfunction "CAP1_NC_48") (pintype "passive"))
    )
    (net (code "144") (name "unconnected-(U2-CAP2_NC-Pad47)") (class "Default")
      (node (ref "U2") (pin "47") (pinfunction "CAP2_NC_47") (pintype "passive"))
    )
    (net (code "145") (name "unconnected-(U2-VDD_SDIO_NC-Pad26)") (class "Default")
      (node (ref "U2") (pin "26") (pinfunction "VDD_SDIO_NC_26") (pintype "passive"))
    )
    (net (code "146") (name "unconnected-(U2-XTAL_N_NC-Pad44)") (class "Default")
      (node (ref "U2") (pin "44") (pinfunction "XTAL_N_NC_44") (pintype "passive"))
    )
    (net (code "147") (name "unconnected-(U2-XTAL_P_NC-Pad45)") (class "Default")
      (node (ref "U2") (pin "45") (pinfunction "XTAL_P_NC_45") (pintype "passive"))
    )
    (net (code "148") (name "unconnected-(U5-NC-Pad5)") (class "Default")
      (node (ref "U5") (pin "5") (pinfunction "NC_5") (pintype "passive"))
    )
    (net (code "149") (name "unconnected-(U5-NC-Pad8)") (class "Default")
      (node (ref "U5") (pin "8") (pinfunction "NC_8") (pintype "passive"))
    )
  )
)
